# outputmixer.net
KiCad netlist of a schematic drawn in Altium Designer
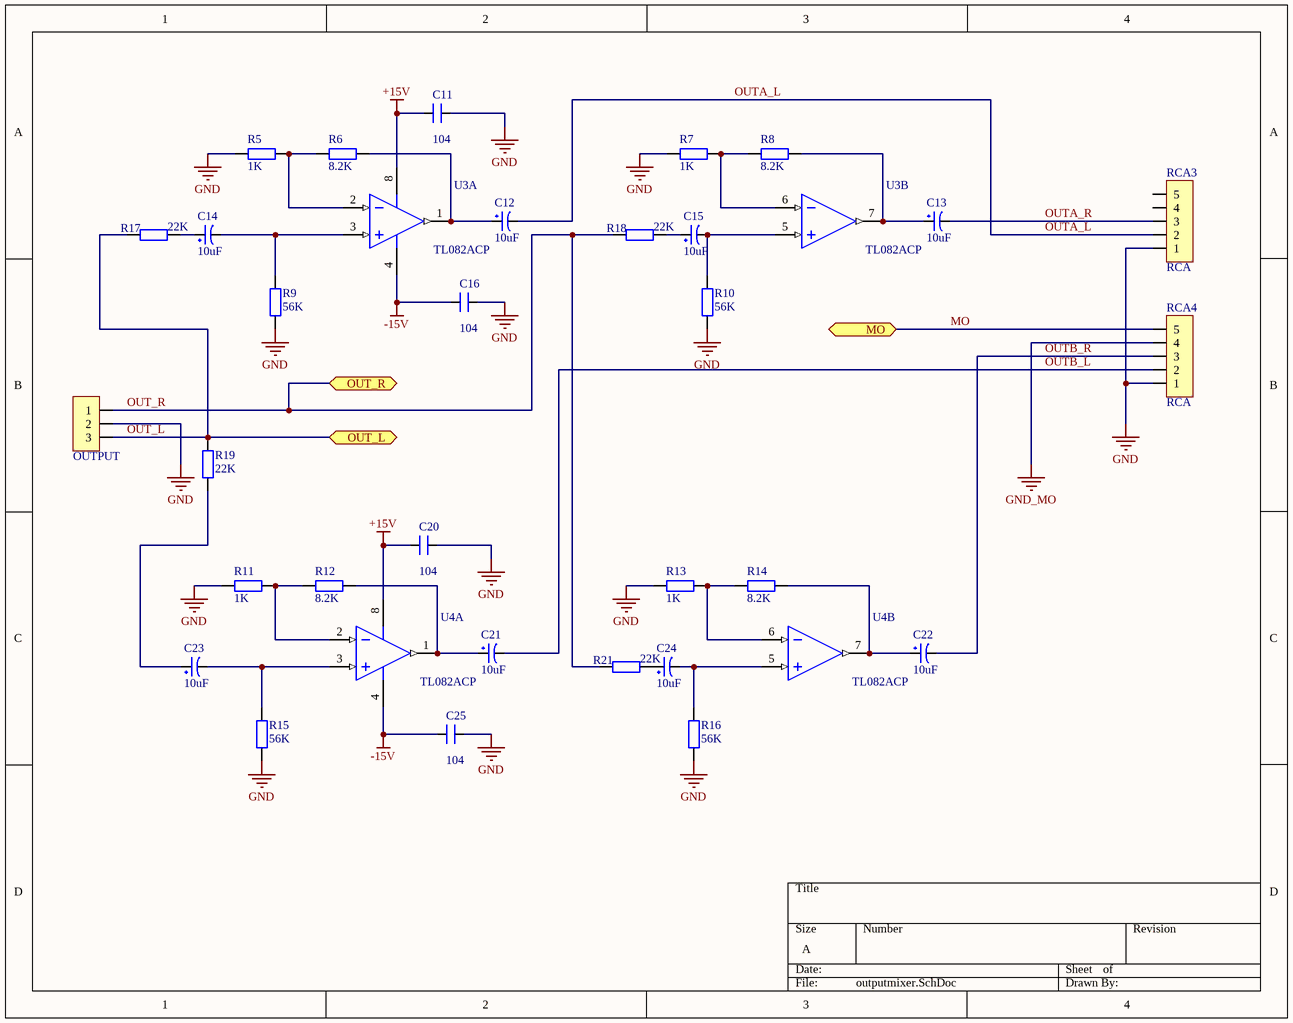
[diagram p0: outputmixer.SchDoc]

(export (version "E")
  (design (tool "Eeschema 10.0.6"))
  (components
    (comp (ref "C11")
      (value "104")
      (footprint "TU_GOM(104-->105pF)")
      (libsource (lib "MH_DA_THU_VIEN_16122016") (part "TU_MICA_ 104 100V(2A104J)_MH"))
    )
    (comp (ref "C12")
      (value "10uF")
      (footprint "CAP5x12")
      (description "TU_HOA_4.7uF_100V_MH")
      (libsource (lib "MH_DA_THU_VIEN_16122016") (part "TU_HOA_4.7uF_100V_MH"))
    )
    (comp (ref "C13")
      (value "10uF")
      (footprint "CAP5x12")
      (description "TU_HOA_4.7uF_100V_MH")
      (libsource (lib "MH_DA_THU_VIEN_16122016") (part "TU_HOA_4.7uF_100V_MH"))
    )
    (comp (ref "C14")
      (value "10uF")
      (footprint "CAP5x12")
      (libsource (lib "MH_DA_THU_VIEN_16122016") (part "TU_HOA_10uF_16V_MH"))
    )
    (comp (ref "C15")
      (value "10uF")
      (footprint "CAP5x12")
      (libsource (lib "MH_DA_THU_VIEN_16122016") (part "TU_HOA_10uF_16V_MH"))
    )
    (comp (ref "C16")
      (value "104")
      (footprint "TU_GOM(104-->105pF)")
      (libsource (lib "MH_DA_THU_VIEN_16122016") (part "TU_MICA_ 104 100V(2A104J)_MH"))
    )
    (comp (ref "C20")
      (value "104")
      (footprint "TU_GOM(104-->105pF)")
      (libsource (lib "MH_DA_THU_VIEN_16122016") (part "TU_MICA_ 104 100V(2A104J)_MH"))
    )
    (comp (ref "C21")
      (value "10uF")
      (footprint "CAP5x12")
      (description "TU_HOA_4.7uF_100V_MH")
      (libsource (lib "MH_DA_THU_VIEN_16122016") (part "TU_HOA_4.7uF_100V_MH"))
    )
    (comp (ref "C22")
      (value "10uF")
      (footprint "CAP5x12")
      (description "TU_HOA_4.7uF_100V_MH")
      (libsource (lib "MH_DA_THU_VIEN_16122016") (part "TU_HOA_4.7uF_100V_MH"))
    )
    (comp (ref "C23")
      (value "10uF")
      (footprint "CAP5x12")
      (libsource (lib "MH_DA_THU_VIEN_16122016") (part "TU_HOA_10uF_16V_MH"))
    )
    (comp (ref "C24")
      (value "10uF")
      (footprint "CAP5x12")
      (libsource (lib "MH_DA_THU_VIEN_16122016") (part "TU_HOA_10uF_16V_MH"))
    )
    (comp (ref "C25")
      (value "104")
      (footprint "TU_GOM(104-->105pF)")
      (libsource (lib "MH_DA_THU_VIEN_16122016") (part "TU_MICA_ 104 100V(2A104J)_MH"))
    )
    (comp (ref "OUTPUT")
      (value "Header 3_MH")
      (footprint "HEADER 3")
      (description "Header 3P XH2.54 thẳng")
      (libsource (lib "MH_DA_THU_VIEN_16122016") (part "Header 3_MH"))
    )
    (comp (ref "R5")
      (value "1K")
      (footprint "TRO_VACH_ 1/4W")
      (libsource (lib "MH_DA_THU_VIEN_16122016") (part "TRO_VACH_1/4W_MH"))
    )
    (comp (ref "R6")
      (value "8.2K")
      (footprint "TRO_VACH_ 1/4W")
      (libsource (lib "MH_DA_THU_VIEN_16122016") (part "TRO_VACH_1/4W_MH"))
    )
    (comp (ref "R7")
      (value "1K")
      (footprint "TRO_VACH_ 1/4W")
      (libsource (lib "MH_DA_THU_VIEN_16122016") (part "TRO_VACH_1/4W_MH"))
    )
    (comp (ref "R8")
      (value "8.2K")
      (footprint "TRO_VACH_ 1/4W")
      (libsource (lib "MH_DA_THU_VIEN_16122016") (part "TRO_VACH_1/4W_MH"))
    )
    (comp (ref "R9")
      (value "56K")
      (footprint "TRO_VACH_ 1/4W")
      (libsource (lib "MH_DA_THU_VIEN_16122016") (part "TRO_VACH_1/4W_MH"))
    )
    (comp (ref "R10")
      (value "56K")
      (footprint "TRO_VACH_ 1/4W")
      (libsource (lib "MH_DA_THU_VIEN_16122016") (part "TRO_VACH_1/4W_MH"))
    )
    (comp (ref "R11")
      (value "1K")
      (footprint "TRO_VACH_ 1/4W")
      (libsource (lib "MH_DA_THU_VIEN_16122016") (part "TRO_VACH_1/4W_MH"))
    )
    (comp (ref "R12")
      (value "8.2K")
      (footprint "TRO_VACH_ 1/4W")
      (libsource (lib "MH_DA_THU_VIEN_16122016") (part "TRO_VACH_1/4W_MH"))
    )
    (comp (ref "R13")
      (value "1K")
      (footprint "TRO_VACH_ 1/4W")
      (libsource (lib "MH_DA_THU_VIEN_16122016") (part "TRO_VACH_1/4W_MH"))
    )
    (comp (ref "R14")
      (value "8.2K")
      (footprint "TRO_VACH_ 1/4W")
      (libsource (lib "MH_DA_THU_VIEN_16122016") (part "TRO_VACH_1/4W_MH"))
    )
    (comp (ref "R15")
      (value "56K")
      (footprint "TRO_VACH_ 1/4W")
      (libsource (lib "MH_DA_THU_VIEN_16122016") (part "TRO_VACH_1/4W_MH"))
    )
    (comp (ref "R16")
      (value "56K")
      (footprint "TRO_VACH_ 1/4W")
      (libsource (lib "MH_DA_THU_VIEN_16122016") (part "TRO_VACH_1/4W_MH"))
    )
    (comp (ref "R17")
      (value "22K")
      (footprint "TRO_VACH_ 1/4W")
      (libsource (lib "MH_DA_THU_VIEN_16122016") (part "TRO_VACH_1/4W_MH"))
    )
    (comp (ref "R18")
      (value "22K")
      (footprint "TRO_VACH_ 1/4W")
      (libsource (lib "MH_DA_THU_VIEN_16122016") (part "TRO_VACH_1/4W_MH"))
    )
    (comp (ref "R19")
      (value "22K")
      (footprint "TRO_VACH_ 1/4W")
      (libsource (lib "MH_DA_THU_VIEN_16122016") (part "TRO_VACH_1/4W_MH"))
    )
    (comp (ref "R21")
      (value "22K")
      (footprint "TRO_VACH_ 1/4W")
      (libsource (lib "MH_DA_THU_VIEN_16122016") (part "TRO_VACH_1/4W_MH"))
    )
    (comp (ref "RCA3")
      (value "RCA")
      (footprint "RCA3P")
      (description "Header 5P XH2.54 thẳng")
      (libsource (lib "MH_DA_THU_VIEN_16122016") (part "Header 5_MH"))
    )
    (comp (ref "RCA4")
      (value "RCA")
      (footprint "RCA3P")
      (description "Header 5P XH2.54 thẳng")
      (libsource (lib "MH_DA_THU_VIEN_16122016") (part "Header 5_MH"))
    )
    (comp (ref "U3")
      (value "TL082ACP")
      (footprint "DIP8")
      (description "JFET-Input Operational Amplifier")
      (fields (field (name "PUBLISHER") "Altium Limited"))
      (libsource (lib "Schlib1") (part "TL082ACP"))
    )
    (comp (ref "U4")
      (value "TL082ACP")
      (footprint "DIP8")
      (description "JFET-Input Operational Amplifier")
      (fields (field (name "PUBLISHER") "Altium Limited"))
      (libsource (lib "Schlib1") (part "TL082ACP"))
    )
  )
  (nets
    (net (code "1") (name "+15V") (class "Default")
      (node (ref "C11") (pin "1") (pinfunction "1_1") (pintype "passive"))
      (node (ref "C20") (pin "1") (pinfunction "1_1") (pintype "passive"))
      (node (ref "U3") (pin "8") (pinfunction "V+_8") (pintype "power_in"))
      (node (ref "U4") (pin "8") (pinfunction "V+_8") (pintype "power_in"))
    )
    (net (code "2") (name "-15V") (class "Default")
      (node (ref "C16") (pin "1") (pinfunction "1_1") (pintype "passive"))
      (node (ref "C25") (pin "1") (pinfunction "1_1") (pintype "passive"))
      (node (ref "U3") (pin "4") (pinfunction "V-_4") (pintype "power_in"))
      (node (ref "U4") (pin "4") (pinfunction "V-_4") (pintype "power_in"))
    )
    (net (code "3") (name "/MO") (class "Default")
      (node (ref "RCA4") (pin "5") (pinfunction "5_5") (pintype "passive"))
    )
    (net (code "4") (name "/OUTA_L") (class "Default")
      (node (ref "C12") (pin "2") (pinfunction "2_2") (pintype "passive"))
      (node (ref "RCA3") (pin "2") (pinfunction "2_2") (pintype "passive"))
    )
    (net (code "5") (name "/OUTA_R") (class "Default")
      (node (ref "C13") (pin "2") (pinfunction "2_2") (pintype "passive"))
      (node (ref "RCA3") (pin "3") (pinfunction "3_3") (pintype "passive"))
    )
    (net (code "6") (name "/OUTB_L") (class "Default")
      (node (ref "C21") (pin "2") (pinfunction "2_2") (pintype "passive"))
      (node (ref "RCA4") (pin "2") (pinfunction "2_2") (pintype "passive"))
    )
    (net (code "7") (name "/OUTB_R") (class "Default")
      (node (ref "C22") (pin "2") (pinfunction "2_2") (pintype "passive"))
      (node (ref "RCA4") (pin "3") (pinfunction "3_3") (pintype "passive"))
    )
    (net (code "8") (name "/OUT_L") (class "Default")
      (node (ref "OUTPUT") (pin "3") (pinfunction "3_3") (pintype "passive"))
      (node (ref "R17") (pin "1") (pinfunction "1_1") (pintype "passive"))
      (node (ref "R19") (pin "2") (pinfunction "2_2") (pintype "passive"))
    )
    (net (code "9") (name "/OUT_R") (class "Default")
      (node (ref "OUTPUT") (pin "1") (pinfunction "1_1") (pintype "passive"))
      (node (ref "R18") (pin "1") (pinfunction "1_1") (pintype "passive"))
      (node (ref "R21") (pin "1") (pinfunction "1_1") (pintype "passive"))
    )
    (net (code "10") (name "GND") (class "Default")
      (node (ref "C11") (pin "2") (pinfunction "2_2") (pintype "passive"))
      (node (ref "C16") (pin "2") (pinfunction "2_2") (pintype "passive"))
      (node (ref "C20") (pin "2") (pinfunction "2_2") (pintype "passive"))
      (node (ref "C25") (pin "2") (pinfunction "2_2") (pintype "passive"))
      (node (ref "OUTPUT") (pin "2") (pinfunction "2_2") (pintype "passive"))
      (node (ref "R10") (pin "1") (pinfunction "1_1") (pintype "passive"))
      (node (ref "R11") (pin "1") (pinfunction "1_1") (pintype "passive"))
      (node (ref "R13") (pin "1") (pinfunction "1_1") (pintype "passive"))
      (node (ref "R15") (pin "1") (pinfunction "1_1") (pintype "passive"))
      (node (ref "R16") (pin "1") (pinfunction "1_1") (pintype "passive"))
      (node (ref "R5") (pin "1") (pinfunction "1_1") (pintype "passive"))
      (node (ref "R7") (pin "1") (pinfunction "1_1") (pintype "passive"))
      (node (ref "R9") (pin "1") (pinfunction "1_1") (pintype "passive"))
      (node (ref "RCA3") (pin "1") (pinfunction "1_1") (pintype "passive"))
      (node (ref "RCA4") (pin "1") (pinfunction "1_1") (pintype "passive"))
    )
    (net (code "11") (name "GND_MO") (class "Default")
      (node (ref "RCA4") (pin "4") (pinfunction "4_4") (pintype "passive"))
    )
    (net (code "12") (name "Net-(C14-Pad1)") (class "Default")
      (node (ref "C14") (pin "1") (pinfunction "1_1") (pintype "passive"))
      (node (ref "R17") (pin "2") (pinfunction "2_2") (pintype "passive"))
    )
    (net (code "13") (name "Net-(C15-Pad1)") (class "Default")
      (node (ref "C15") (pin "1") (pinfunction "1_1") (pintype "passive"))
      (node (ref "R18") (pin "2") (pinfunction "2_2") (pintype "passive"))
    )
    (net (code "14") (name "Net-(C23-Pad1)") (class "Default")
      (node (ref "C23") (pin "1") (pinfunction "1_1") (pintype "passive"))
      (node (ref "R19") (pin "1") (pinfunction "1_1") (pintype "passive"))
    )
    (net (code "15") (name "Net-(C24-Pad1)") (class "Default")
      (node (ref "C24") (pin "1") (pinfunction "1_1") (pintype "passive"))
      (node (ref "R21") (pin "2") (pinfunction "2_2") (pintype "passive"))
    )
    (net (code "16") (name "Net-(U3A-IN+)") (class "Default")
      (node (ref "C14") (pin "2") (pinfunction "2_2") (pintype "passive"))
      (node (ref "R9") (pin "2") (pinfunction "2_2") (pintype "passive"))
      (node (ref "U3") (pin "3") (pinfunction "IN+_3") (pintype "input"))
    )
    (net (code "17") (name "Net-(U3A-IN-)") (class "Default")
      (node (ref "R5") (pin "2") (pinfunction "2_2") (pintype "passive"))
      (node (ref "R6") (pin "2") (pinfunction "2_2") (pintype "passive"))
      (node (ref "U3") (pin "2") (pinfunction "IN-_2") (pintype "input"))
    )
    (net (code "18") (name "Net-(U3A-OUT)") (class "Default")
      (node (ref "C12") (pin "1") (pinfunction "1_1") (pintype "passive"))
      (node (ref "R6") (pin "1") (pinfunction "1_1") (pintype "passive"))
      (node (ref "U3") (pin "1") (pinfunction "OUT_1") (pintype "output"))
    )
    (net (code "19") (name "Net-(U3B-IN+)") (class "Default")
      (node (ref "C15") (pin "2") (pinfunction "2_2") (pintype "passive"))
      (node (ref "R10") (pin "2") (pinfunction "2_2") (pintype "passive"))
      (node (ref "U3") (pin "5") (pinfunction "IN+_5") (pintype "input"))
    )
    (net (code "20") (name "Net-(U3B-IN-)") (class "Default")
      (node (ref "R7") (pin "2") (pinfunction "2_2") (pintype "passive"))
      (node (ref "R8") (pin "2") (pinfunction "2_2") (pintype "passive"))
      (node (ref "U3") (pin "6") (pinfunction "IN-_6") (pintype "input"))
    )
    (net (code "21") (name "Net-(U3B-OUT)") (class "Default")
      (node (ref "C13") (pin "1") (pinfunction "1_1") (pintype "passive"))
      (node (ref "R8") (pin "1") (pinfunction "1_1") (pintype "passive"))
      (node (ref "U3") (pin "7") (pinfunction "OUT_7") (pintype "output"))
    )
    (net (code "22") (name "Net-(U4A-IN+)") (class "Default")
      (node (ref "C23") (pin "2") (pinfunction "2_2") (pintype "passive"))
      (node (ref "R15") (pin "2") (pinfunction "2_2") (pintype "passive"))
      (node (ref "U4") (pin "3") (pinfunction "IN+_3") (pintype "input"))
    )
    (net (code "23") (name "Net-(U4A-IN-)") (class "Default")
      (node (ref "R11") (pin "2") (pinfunction "2_2") (pintype "passive"))
      (node (ref "R12") (pin "2") (pinfunction "2_2") (pintype "passive"))
      (node (ref "U4") (pin "2") (pinfunction "IN-_2") (pintype "input"))
    )
    (net (code "24") (name "Net-(U4A-OUT)") (class "Default")
      (node (ref "C21") (pin "1") (pinfunction "1_1") (pintype "passive"))
      (node (ref "R12") (pin "1") (pinfunction "1_1") (pintype "passive"))
      (node (ref "U4") (pin "1") (pinfunction "OUT_1") (pintype "output"))
    )
    (net (code "25") (name "Net-(U4B-IN+)") (class "Default")
      (node (ref "C24") (pin "2") (pinfunction "2_2") (pintype "passive"))
      (node (ref "R16") (pin "2") (pinfunction "2_2") (pintype "passive"))
      (node (ref "U4") (pin "5") (pinfunction "IN+_5") (pintype "input"))
    )
    (net (code "26") (name "Net-(U4B-IN-)") (class "Default")
      (node (ref "R13") (pin "2") (pinfunction "2_2") (pintype "passive"))
      (node (ref "R14") (pin "2") (pinfunction "2_2") (pintype "passive"))
      (node (ref "U4") (pin "6") (pinfunction "IN-_6") (pintype "input"))
    )
    (net (code "27") (name "Net-(U4B-OUT)") (class "Default")
      (node (ref "C22") (pin "1") (pinfunction "1_1") (pintype "passive"))
      (node (ref "R14") (pin "1") (pinfunction "1_1") (pintype "passive"))
      (node (ref "U4") (pin "7") (pinfunction "OUT_7") (pintype "output"))
    )
    (net (code "28") (name "unconnected-(RCA3-Pad4)") (class "Default")
      (node (ref "RCA3") (pin "4") (pinfunction "4_4") (pintype "passive"))
    )
    (net (code "29") (name "unconnected-(RCA3-Pad5)") (class "Default")
      (node (ref "RCA3") (pin "5") (pinfunction "5_5") (pintype "passive"))
    )
  )
)
